# TDDswitches.net
KiCad netlist of a schematic drawn in Altium Designer
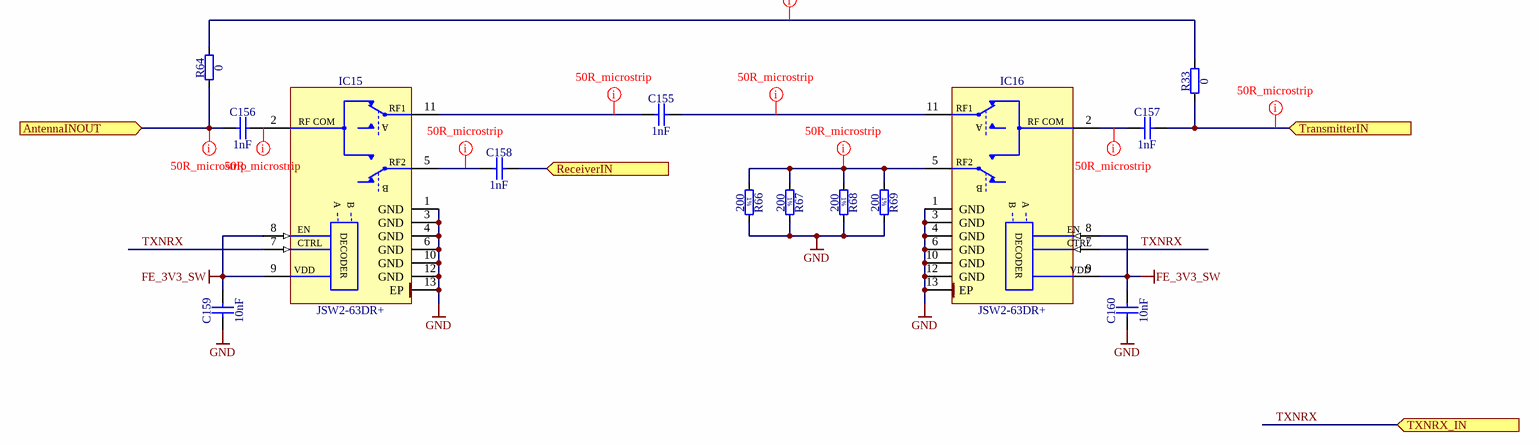
[diagram p0: TDDswitches.SchDoc]

(export (version "E")
  (design (tool "Eeschema 10.0.6"))
  (components
    (comp (ref "C155")
      (value "1nF")
      (footprint "CAPC1005X55N")
      (description "Non-polarised capacitor")
      (fields
        (field (name "PART NUMBER") "CC0402_1NF_50V_10%_X7R")
        (field (name "VOLTAGE") "50V")
        (field (name "AUTHOR") "CERN DEM JLC")
      )
      (libsource (lib "Capacitors") (part "Capacitor - non polarized"))
    )
    (comp (ref "C156")
      (value "1nF")
      (footprint "CAPC1005X55N")
      (description "Non-polarised capacitor")
      (fields
        (field (name "PART NUMBER") "CC0402_1NF_50V_10%_X7R")
        (field (name "VOLTAGE") "50V")
        (field (name "AUTHOR") "CERN DEM JLC")
      )
      (libsource (lib "Capacitors") (part "Capacitor - non polarized"))
    )
    (comp (ref "C157")
      (value "1nF")
      (footprint "CAPC1005X55N")
      (description "Non-polarised capacitor")
      (fields
        (field (name "PART NUMBER") "CC0402_1NF_50V_10%_X7R")
        (field (name "VOLTAGE") "50V")
        (field (name "AUTHOR") "CERN DEM JLC")
      )
      (libsource (lib "Capacitors") (part "Capacitor - non polarized"))
    )
    (comp (ref "C158")
      (value "1nF")
      (footprint "CAPC1005X55N")
      (description "Non-polarised capacitor")
      (fields
        (field (name "PART NUMBER") "CC0402_1NF_50V_10%_X7R")
        (field (name "VOLTAGE") "50V")
        (field (name "AUTHOR") "CERN DEM JLC")
      )
      (libsource (lib "Capacitors") (part "Capacitor - non polarized"))
    )
    (comp (ref "C159")
      (value "10nF")
      (footprint "CAPC1005X55N")
      (description "Non-polarised capacitor")
      (fields
        (field (name "PART NUMBER") "CC0402_10NF_50V_10%_X7R")
        (field (name "VOLTAGE") "50V")
        (field (name "AUTHOR") "CERN DEM MR")
      )
      (libsource (lib "Capacitors") (part "Capacitor - non polarized"))
    )
    (comp (ref "C160")
      (value "10nF")
      (footprint "CAPC1005X55N")
      (description "Non-polarised capacitor")
      (fields
        (field (name "PART NUMBER") "CC0402_10NF_50V_10%_X7R")
        (field (name "VOLTAGE") "50V")
        (field (name "AUTHOR") "CERN DEM MR")
      )
      (libsource (lib "Capacitors") (part "Capacitor - non polarized"))
    )
    (comp (ref "IC15")
      (value "JSW2-63DR+")
      (footprint "MINI-CIRCUITS_MT1818")
      (description "SPDT RF Switch, 50 Ohm, 5 to 6000MHz, High Power 3W")
      (fields (field (name "MANUFACTURER") "MINI-CIRCUITS") (field (name "AUTHOR") "CERN DEM JMW"))
      (libsource (lib "ICs And Semiconductors") (part "JSW2-63DR+"))
    )
    (comp (ref "IC16")
      (value "JSW2-63DR+")
      (footprint "MINI-CIRCUITS_MT1818")
      (description "SPDT RF Switch, 50 Ohm, 5 to 6000MHz, High Power 3W")
      (fields (field (name "MANUFACTURER") "MINI-CIRCUITS") (field (name "AUTHOR") "CERN DEM JMW"))
      (libsource (lib "") (part "JSW2-63DR+_1"))
    )
    (comp (ref "R33")
      (value "0")
      (footprint "RESC1005X40N")
      (description "Resistor")
      (fields
        (field (name "PART NUMBER") "R0402_0R_JUMPER")
        (field (name "MANUFACTURER") "GENERIC")
        (field (name "AUTHOR") "CERN DEM JLC")
      )
      (libsource (lib "Resistors") (part "Resistor"))
    )
    (comp (ref "R64")
      (value "0")
      (footprint "RESC1005X40N")
      (description "Resistor")
      (fields
        (field (name "PART NUMBER") "R0402_0R_JUMPER")
        (field (name "MANUFACTURER") "GENERIC")
        (field (name "AUTHOR") "CERN DEM JLC")
      )
      (libsource (lib "Resistors") (part "Resistor"))
    )
    (comp (ref "R66")
      (value "200")
      (footprint "RESC3216X65N")
      (description "Resistor - 1%")
      (fields
        (field (name "PART NUMBER") "R1206_200R_1%_0.25W_100PPM")
        (field (name "POWER") "0.25W")
        (field (name "AUTHOR") "CERN DEM JLC")
      )
      (libsource (lib "Resistors") (part "Resistor - 1%"))
    )
    (comp (ref "R67")
      (value "200")
      (footprint "RESC3216X65N")
      (description "Resistor - 1%")
      (fields
        (field (name "PART NUMBER") "R1206_200R_1%_0.25W_100PPM")
        (field (name "POWER") "0.25W")
        (field (name "AUTHOR") "CERN DEM JLC")
      )
      (libsource (lib "Resistors") (part "Resistor - 1%"))
    )
    (comp (ref "R68")
      (value "200")
      (footprint "RESC3216X65N")
      (description "Resistor - 1%")
      (fields
        (field (name "PART NUMBER") "R1206_200R_1%_0.25W_100PPM")
        (field (name "POWER") "0.25W")
        (field (name "AUTHOR") "CERN DEM JLC")
      )
      (libsource (lib "Resistors") (part "Resistor - 1%"))
    )
    (comp (ref "R69")
      (value "200")
      (footprint "RESC3216X65N")
      (description "Resistor - 1%")
      (fields
        (field (name "PART NUMBER") "R1206_200R_1%_0.25W_100PPM")
        (field (name "POWER") "0.25W")
        (field (name "AUTHOR") "CERN DEM JLC")
      )
      (libsource (lib "Resistors") (part "Resistor - 1%"))
    )
  )
  (nets
    (net (code "1") (name "/AntennaINOUT") (class "Default")
      (node (ref "C156") (pin "1") (pinfunction "1_1") (pintype "passive"))
      (node (ref "R64") (pin "1") (pinfunction "1_1") (pintype "passive"))
    )
    (net (code "2") (name "/ReceiverIN") (class "Default")
      (node (ref "C158") (pin "2") (pinfunction "2_2") (pintype "passive"))
    )
    (net (code "3") (name "/TXNRX") (class "Default")
      (node (ref "IC15") (pin "7") (pinfunction "CTRL_7") (pintype "input"))
      (node (ref "IC16") (pin "7") (pinfunction "CTRL_7") (pintype "input"))
    )
    (net (code "4") (name "/TransmitterIN") (class "Default")
      (node (ref "C157") (pin "2") (pinfunction "2_2") (pintype "passive"))
      (node (ref "R33") (pin "1") (pinfunction "1_1") (pintype "passive"))
    )
    (net (code "5") (name "FE_3V3_SW") (class "Default")
      (node (ref "C159") (pin "2") (pinfunction "2_2") (pintype "passive"))
      (node (ref "C160") (pin "2") (pinfunction "2_2") (pintype "passive"))
      (node (ref "IC15") (pin "8") (pinfunction "EN_8") (pintype "input"))
      (node (ref "IC15") (pin "9") (pinfunction "VDD_9") (pintype "power_in"))
      (node (ref "IC16") (pin "8") (pinfunction "EN_8") (pintype "input"))
      (node (ref "IC16") (pin "9") (pinfunction "VDD_9") (pintype "power_in"))
    )
    (net (code "6") (name "GND") (class "Default")
      (node (ref "C159") (pin "1") (pinfunction "1_1") (pintype "passive"))
      (node (ref "C160") (pin "1") (pinfunction "1_1") (pintype "passive"))
      (node (ref "IC15") (pin "1") (pinfunction "GND_1") (pintype "power_in"))
      (node (ref "IC15") (pin "10") (pinfunction "GND_10") (pintype "power_in"))
      (node (ref "IC15") (pin "12") (pinfunction "GND_12") (pintype "power_in"))
      (node (ref "IC15") (pin "13") (pinfunction "EP_13") (pintype "power_in"))
      (node (ref "IC15") (pin "3") (pinfunction "GND_3") (pintype "power_in"))
      (node (ref "IC15") (pin "4") (pinfunction "GND_4") (pintype "power_in"))
      (node (ref "IC15") (pin "6") (pinfunction "GND_6") (pintype "power_in"))
      (node (ref "IC16") (pin "1") (pinfunction "GND_1") (pintype "power_in"))
      (node (ref "IC16") (pin "10") (pinfunction "GND_10") (pintype "power_in"))
      (node (ref "IC16") (pin "12") (pinfunction "GND_12") (pintype "power_in"))
      (node (ref "IC16") (pin "13") (pinfunction "EP_13") (pintype "power_in"))
      (node (ref "IC16") (pin "3") (pinfunction "GND_3") (pintype "power_in"))
      (node (ref "IC16") (pin "4") (pinfunction "GND_4") (pintype "power_in"))
      (node (ref "IC16") (pin "6") (pinfunction "GND_6") (pintype "power_in"))
      (node (ref "R66") (pin "2") (pinfunction "2_2") (pintype "passive"))
      (node (ref "R67") (pin "2") (pinfunction "2_2") (pintype "passive"))
      (node (ref "R68") (pin "2") (pinfunction "2_2") (pintype "passive"))
      (node (ref "R69") (pin "2") (pinfunction "2_2") (pintype "passive"))
    )
    (net (code "7") (name "Net-(IC15-RF1)") (class "Default")
      (node (ref "C155") (pin "1") (pinfunction "1_1") (pintype "passive"))
      (node (ref "IC15") (pin "11") (pinfunction "RF1_11") (pintype "passive"))
    )
    (net (code "8") (name "Net-(IC15-RF2)") (class "Default")
      (node (ref "C158") (pin "1") (pinfunction "1_1") (pintype "passive"))
      (node (ref "IC15") (pin "5") (pinfunction "RF2_5") (pintype "passive"))
    )
    (net (code "9") (name "Net-(IC15-RF_COM)") (class "Default")
      (node (ref "C156") (pin "2") (pinfunction "2_2") (pintype "passive"))
      (node (ref "IC15") (pin "2") (pinfunction "RF_COM_2") (pintype "passive"))
    )
    (net (code "10") (name "Net-(IC16-RF1)") (class "Default")
      (node (ref "C155") (pin "2") (pinfunction "2_2") (pintype "passive"))
      (node (ref "IC16") (pin "11") (pinfunction "RF1_11") (pintype "passive"))
    )
    (net (code "11") (name "Net-(IC16-RF2)") (class "Default")
      (node (ref "IC16") (pin "5") (pinfunction "RF2_5") (pintype "passive"))
      (node (ref "R66") (pin "1") (pinfunction "1_1") (pintype "passive"))
      (node (ref "R67") (pin "1") (pinfunction "1_1") (pintype "passive"))
      (node (ref "R68") (pin "1") (pinfunction "1_1") (pintype "passive"))
      (node (ref "R69") (pin "1") (pinfunction "1_1") (pintype "passive"))
    )
    (net (code "12") (name "Net-(IC16-RF_COM)") (class "Default")
      (node (ref "C157") (pin "1") (pinfunction "1_1") (pintype "passive"))
      (node (ref "IC16") (pin "2") (pinfunction "RF_COM_2") (pintype "passive"))
    )
    (net (code "13") (name "Net-(R33-Pad2)") (class "Default")
      (node (ref "R33") (pin "2") (pinfunction "2_2") (pintype "passive"))
      (node (ref "R64") (pin "2") (pinfunction "2_2") (pintype "passive"))
    )
  )
)
